# Nusbio_SPI_Extension.net
KiCad netlist of a schematic drawn in EAGLE
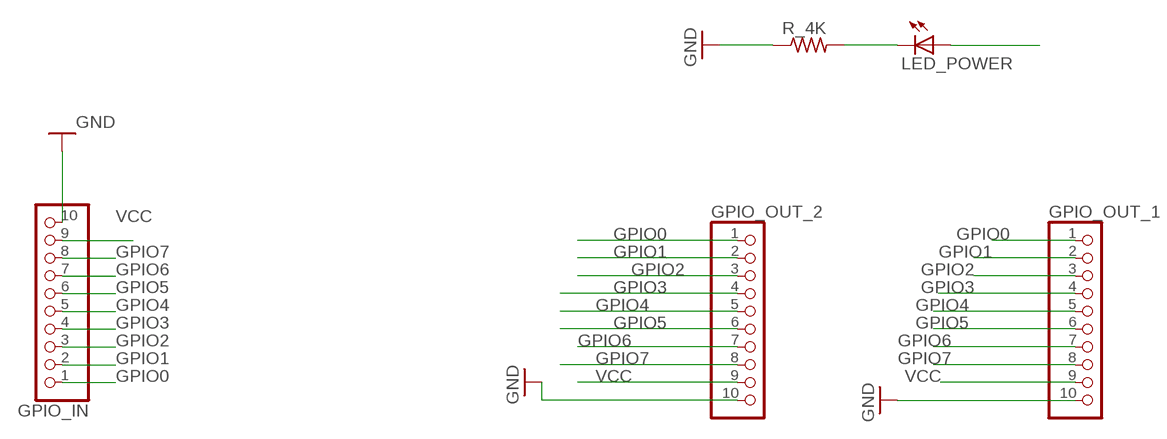
[diagram p0: schematic, sheet 1]

(export (version "E")
  (design (tool "Eeschema 10.0.6"))
  (components
    (comp (ref "GPIO_IN")
      (value "PINHD-1X10")
      (footprint "eagle-import:1X10-BIG")
      (libsource (lib "eagle-import") (part "PINHD-1X10"))
    )
    (comp (ref "GPIO_OUT_1")
      (value "PINHD-1X10")
      (footprint "eagle-import:1X10-BIG")
      (libsource (lib "eagle-import") (part "PINHD-1X10"))
    )
    (comp (ref "GPIO_OUT_2")
      (value "PINHD-1X10")
      (footprint "eagle-import:1X10-BIG")
      (libsource (lib "eagle-import") (part "PINHD-1X10"))
    )
    (comp (ref "LED_POWER")
      (value "LEDSMT1206")
      (footprint "eagle-import:1206")
      (libsource (lib "eagle-import") (part "LEDSMT1206"))
    )
    (comp (ref "R_4K")
      (value "R-US_R1206")
      (footprint "eagle-import:R1206")
      (libsource (lib "eagle-import") (part "R-US_R1206"))
    )
  )
  (nets
    (net (code "1") (name "/GPIO0") (class "Default")
      (node (ref "GPIO_IN") (pin "1") (pinfunction "1_1") (pintype "passive"))
      (node (ref "GPIO_OUT_1") (pin "1") (pinfunction "1_1") (pintype "passive"))
      (node (ref "GPIO_OUT_2") (pin "1") (pinfunction "1_1") (pintype "passive"))
    )
    (net (code "2") (name "/GPIO1") (class "Default")
      (node (ref "GPIO_IN") (pin "2") (pinfunction "2_2") (pintype "passive"))
      (node (ref "GPIO_OUT_1") (pin "2") (pinfunction "2_2") (pintype "passive"))
      (node (ref "GPIO_OUT_2") (pin "2") (pinfunction "2_2") (pintype "passive"))
    )
    (net (code "3") (name "/GPIO2") (class "Default")
      (node (ref "GPIO_IN") (pin "3") (pinfunction "3_3") (pintype "passive"))
      (node (ref "GPIO_OUT_1") (pin "3") (pinfunction "3_3") (pintype "passive"))
      (node (ref "GPIO_OUT_2") (pin "3") (pinfunction "3_3") (pintype "passive"))
    )
    (net (code "4") (name "/GPIO3") (class "Default")
      (node (ref "GPIO_IN") (pin "4") (pinfunction "4_4") (pintype "passive"))
      (node (ref "GPIO_OUT_1") (pin "4") (pinfunction "4_4") (pintype "passive"))
      (node (ref "GPIO_OUT_2") (pin "4") (pinfunction "4_4") (pintype "passive"))
    )
    (net (code "5") (name "/GPIO4") (class "Default")
      (node (ref "GPIO_IN") (pin "5") (pinfunction "5_5") (pintype "passive"))
      (node (ref "GPIO_OUT_1") (pin "5") (pinfunction "5_5") (pintype "passive"))
      (node (ref "GPIO_OUT_2") (pin "5") (pinfunction "5_5") (pintype "passive"))
    )
    (net (code "6") (name "/GPIO5") (class "Default")
      (node (ref "GPIO_IN") (pin "6") (pinfunction "6_6") (pintype "passive"))
      (node (ref "GPIO_OUT_1") (pin "6") (pinfunction "6_6") (pintype "passive"))
      (node (ref "GPIO_OUT_2") (pin "6") (pinfunction "6_6") (pintype "passive"))
    )
    (net (code "7") (name "/GPIO6") (class "Default")
      (node (ref "GPIO_IN") (pin "7") (pinfunction "7_7") (pintype "passive"))
      (node (ref "GPIO_OUT_1") (pin "7") (pinfunction "7_7") (pintype "passive"))
      (node (ref "GPIO_OUT_2") (pin "7") (pinfunction "7_7") (pintype "passive"))
    )
    (net (code "8") (name "/GPIO7") (class "Default")
      (node (ref "GPIO_IN") (pin "8") (pinfunction "8_8") (pintype "passive"))
      (node (ref "GPIO_OUT_1") (pin "8") (pinfunction "8_8") (pintype "passive"))
      (node (ref "GPIO_OUT_2") (pin "8") (pinfunction "8_8") (pintype "passive"))
    )
    (net (code "9") (name "/VCC") (class "Default")
      (node (ref "GPIO_IN") (pin "9") (pinfunction "9_9") (pintype "passive"))
      (node (ref "GPIO_OUT_1") (pin "9") (pinfunction "9_9") (pintype "passive"))
      (node (ref "GPIO_OUT_2") (pin "9") (pinfunction "9_9") (pintype "passive"))
      (node (ref "LED_POWER") (pin "A") (pinfunction "A_A") (pintype "passive"))
    )
    (net (code "10") (name "GND") (class "Default")
      (node (ref "GPIO_IN") (pin "10") (pinfunction "10_10") (pintype "passive"))
      (node (ref "GPIO_OUT_1") (pin "10") (pinfunction "10_10") (pintype "passive"))
      (node (ref "GPIO_OUT_2") (pin "10") (pinfunction "10_10") (pintype "passive"))
      (node (ref "R_4K") (pin "1") (pinfunction "1_1") (pintype "passive"))
    )
    (net (code "11") (name "Net-(LED_POWER-PadC)") (class "Default")
      (node (ref "LED_POWER") (pin "C") (pinfunction "C_C") (pintype "passive"))
      (node (ref "R_4K") (pin "2") (pinfunction "2_2") (pintype "passive"))
    )
  )
)
